# untitled.net
KiCad netlist of a schematic drawn in EAGLE
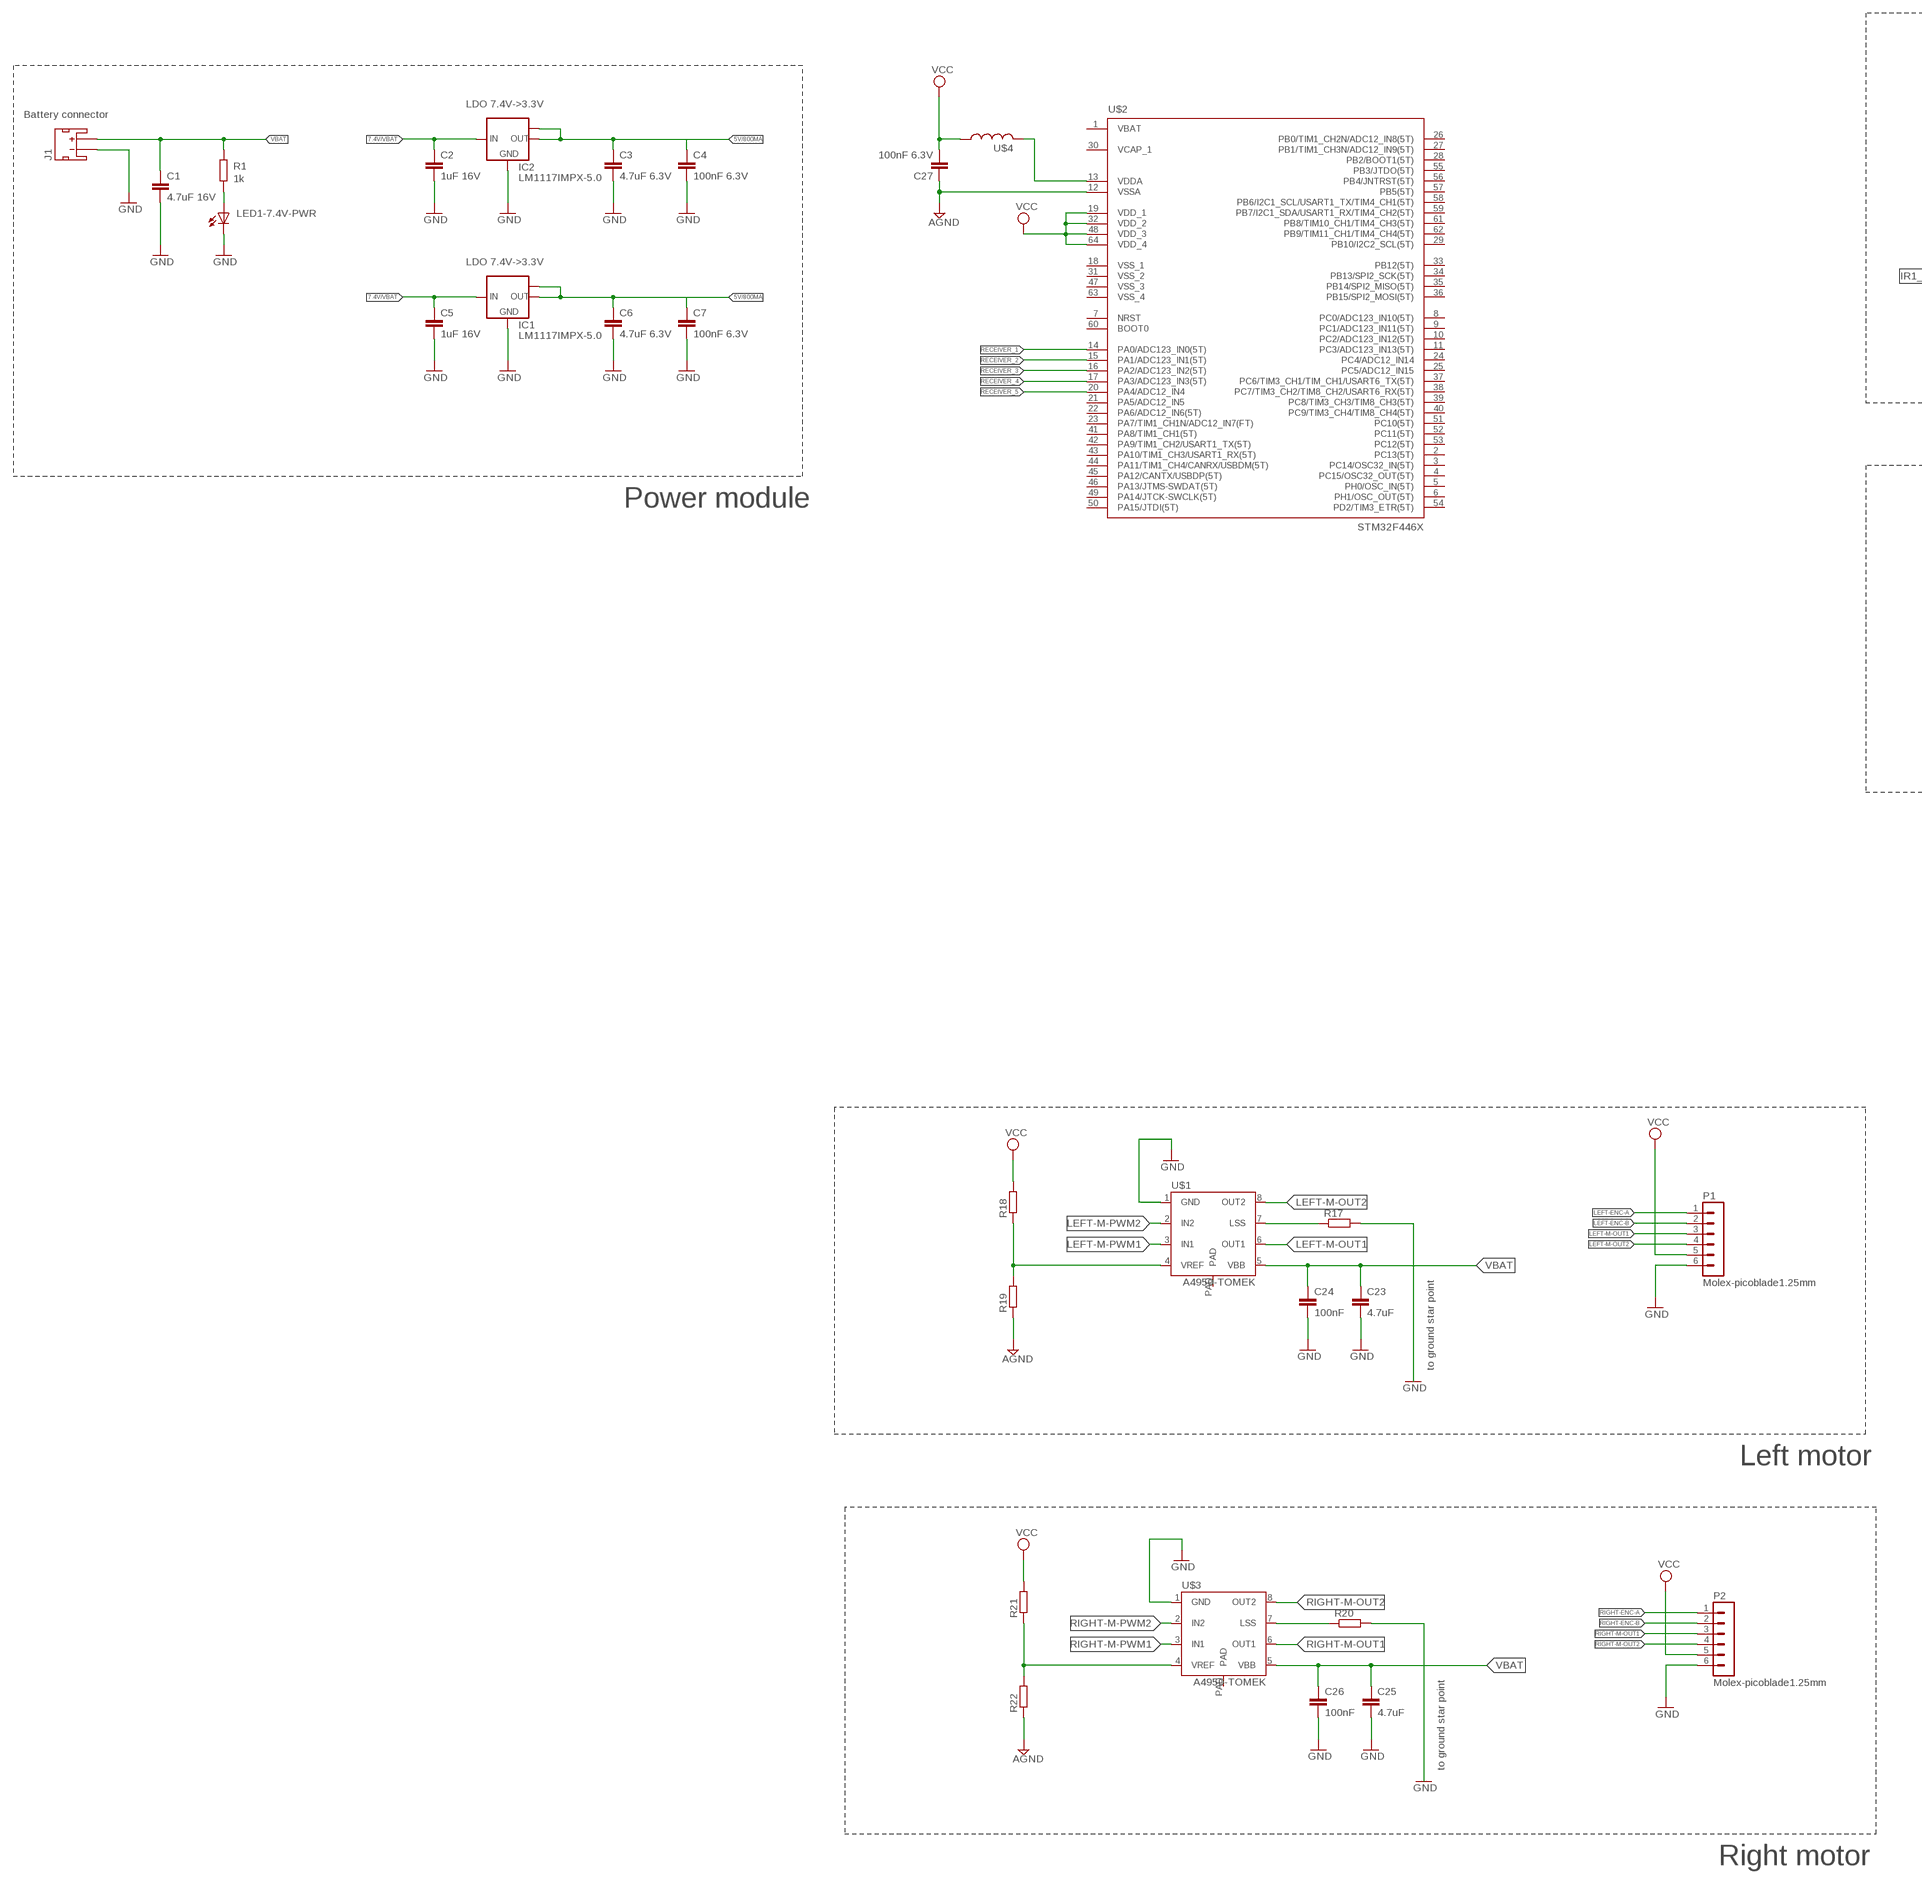
[diagram p0: schematic, sheet 1, part 1 of 2]
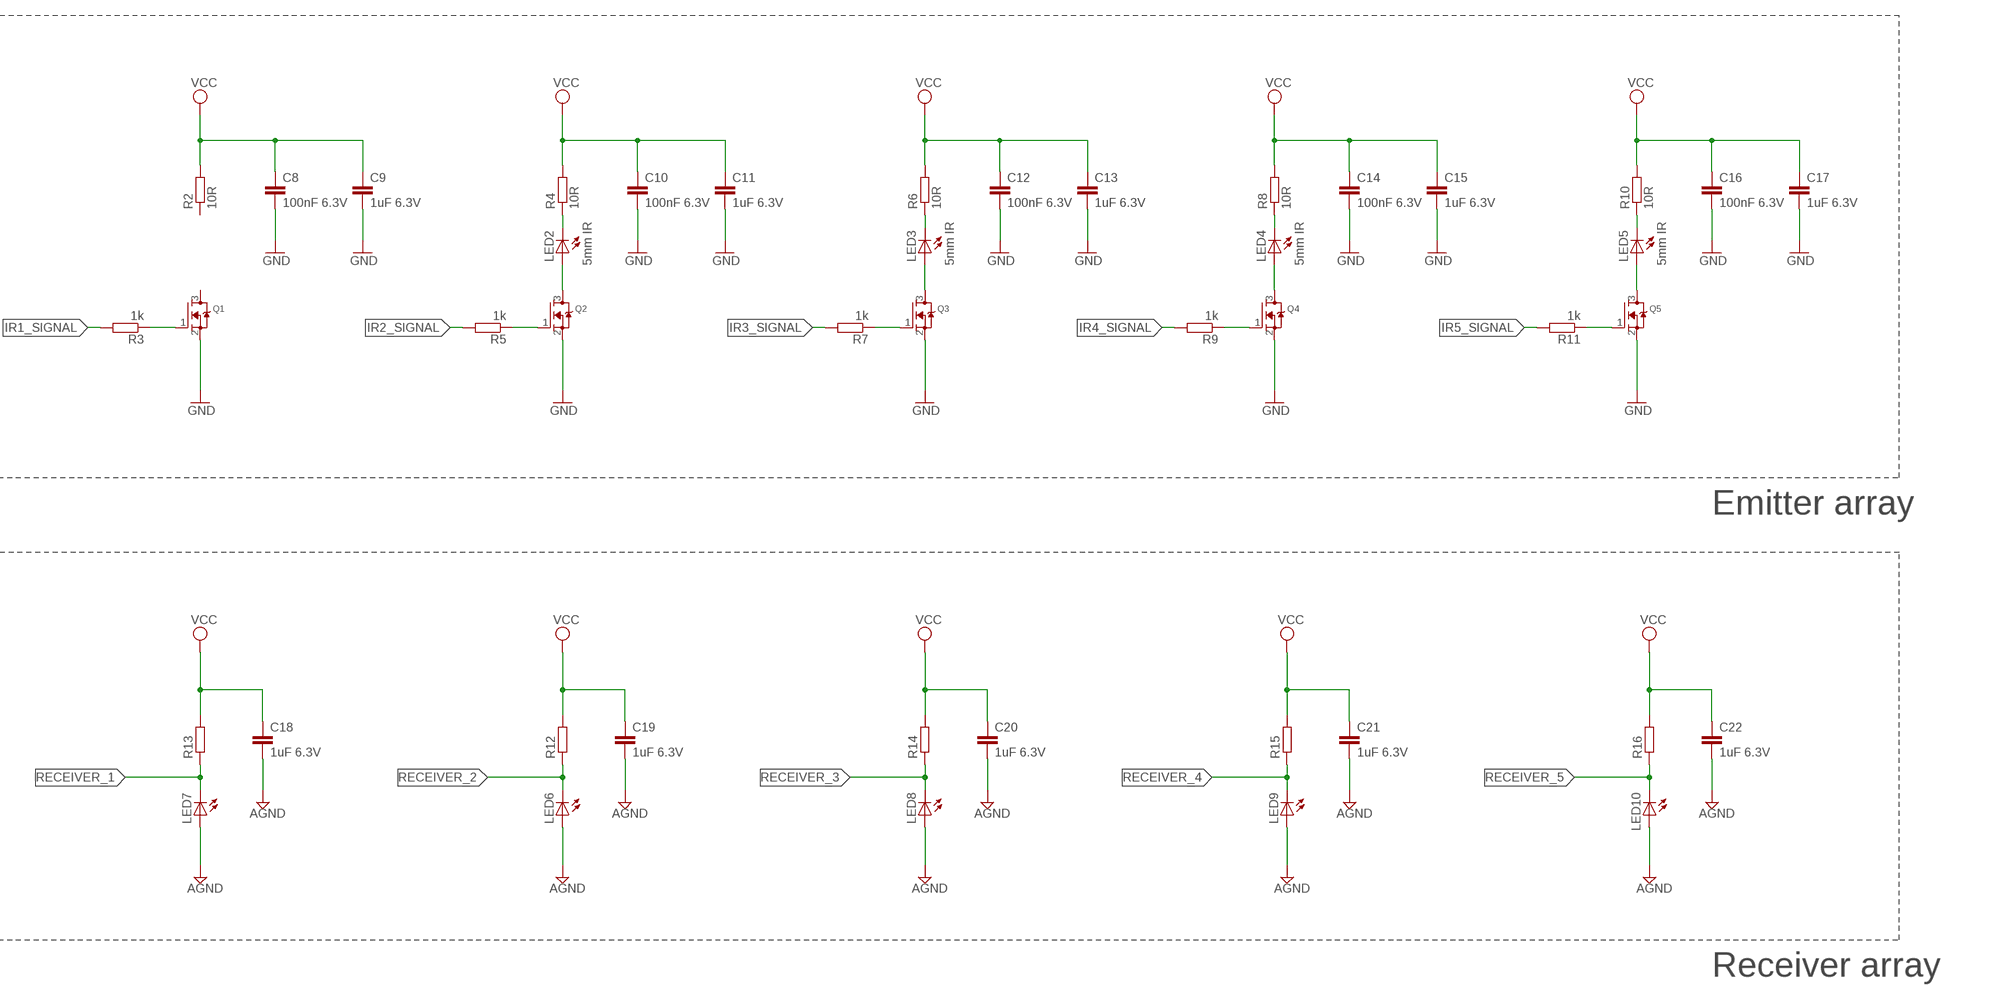
[diagram p1: schematic, sheet 1, part 2 of 2]

(export (version "E")
  (design (tool "Eeschema 10.0.6"))
  (components
    (comp (ref "C1")
      (value "4.7uF 16V")
      (footprint "eagle-import:C0805K")
      (libsource (lib "eagle-import") (part "C-EUC0805K"))
    )
    (comp (ref "C2")
      (value "1uF 16V")
      (footprint "eagle-import:C0805K")
      (libsource (lib "eagle-import") (part "C-EUC0805K"))
    )
    (comp (ref "C3")
      (value "4.7uF 6.3V")
      (footprint "eagle-import:C0805K")
      (libsource (lib "eagle-import") (part "C-EUC0805K"))
    )
    (comp (ref "C4")
      (value "100nF 6.3V")
      (footprint "eagle-import:C0805K")
      (libsource (lib "eagle-import") (part "C-EUC0805K"))
    )
    (comp (ref "C5")
      (value "1uF 16V")
      (footprint "eagle-import:C0805K")
      (libsource (lib "eagle-import") (part "C-EUC0805K"))
    )
    (comp (ref "C6")
      (value "4.7uF 6.3V")
      (footprint "eagle-import:C0805K")
      (libsource (lib "eagle-import") (part "C-EUC0805K"))
    )
    (comp (ref "C7")
      (value "100nF 6.3V")
      (footprint "eagle-import:C0805K")
      (libsource (lib "eagle-import") (part "C-EUC0805K"))
    )
    (comp (ref "C8")
      (value "100nF 6.3V")
      (footprint "eagle-import:C0805K")
      (libsource (lib "eagle-import") (part "C-EUC0805K"))
    )
    (comp (ref "C9")
      (value "1uF 6.3V")
      (footprint "eagle-import:C0805K")
      (libsource (lib "eagle-import") (part "C-EUC0805K"))
    )
    (comp (ref "C10")
      (value "100nF 6.3V")
      (footprint "eagle-import:C0805K")
      (libsource (lib "eagle-import") (part "C-EUC0805K"))
    )
    (comp (ref "C11")
      (value "1uF 6.3V")
      (footprint "eagle-import:C0805K")
      (libsource (lib "eagle-import") (part "C-EUC0805K"))
    )
    (comp (ref "C12")
      (value "100nF 6.3V")
      (footprint "eagle-import:C0805K")
      (libsource (lib "eagle-import") (part "C-EUC0805K"))
    )
    (comp (ref "C13")
      (value "1uF 6.3V")
      (footprint "eagle-import:C0805K")
      (libsource (lib "eagle-import") (part "C-EUC0805K"))
    )
    (comp (ref "C14")
      (value "100nF 6.3V")
      (footprint "eagle-import:C0805K")
      (libsource (lib "eagle-import") (part "C-EUC0805K"))
    )
    (comp (ref "C15")
      (value "1uF 6.3V")
      (footprint "eagle-import:C0805K")
      (libsource (lib "eagle-import") (part "C-EUC0805K"))
    )
    (comp (ref "C16")
      (value "100nF 6.3V")
      (footprint "eagle-import:C0805K")
      (libsource (lib "eagle-import") (part "C-EUC0805K"))
    )
    (comp (ref "C17")
      (value "1uF 6.3V")
      (footprint "eagle-import:C0805K")
      (libsource (lib "eagle-import") (part "C-EUC0805K"))
    )
    (comp (ref "C18")
      (value "1uF 6.3V")
      (footprint "eagle-import:C0805K")
      (libsource (lib "eagle-import") (part "C-EUC0805K"))
    )
    (comp (ref "C19")
      (value "1uF 6.3V")
      (footprint "eagle-import:C0805K")
      (libsource (lib "eagle-import") (part "C-EUC0805K"))
    )
    (comp (ref "C20")
      (value "1uF 6.3V")
      (footprint "eagle-import:C0805K")
      (libsource (lib "eagle-import") (part "C-EUC0805K"))
    )
    (comp (ref "C21")
      (value "1uF 6.3V")
      (footprint "eagle-import:C0805K")
      (libsource (lib "eagle-import") (part "C-EUC0805K"))
    )
    (comp (ref "C22")
      (value "1uF 6.3V")
      (footprint "eagle-import:C0805K")
      (libsource (lib "eagle-import") (part "C-EUC0805K"))
    )
    (comp (ref "C23")
      (value "4.7uF")
      (footprint "eagle-import:C0805K")
      (libsource (lib "eagle-import") (part "C-EUC0805K"))
    )
    (comp (ref "C24")
      (value "100nF")
      (footprint "eagle-import:C0805K")
      (libsource (lib "eagle-import") (part "C-EUC0805K"))
    )
    (comp (ref "C25")
      (value "4.7uF")
      (footprint "eagle-import:C0805K")
      (libsource (lib "eagle-import") (part "C-EUC0805K"))
    )
    (comp (ref "C26")
      (value "100nF")
      (footprint "eagle-import:C0805K")
      (libsource (lib "eagle-import") (part "C-EUC0805K"))
    )
    (comp (ref "C27")
      (value "100nF 6.3V")
      (footprint "eagle-import:C0805K")
      (libsource (lib "eagle-import") (part "C-EUC0805K"))
    )
    (comp (ref "IC1")
      (value "LM1117IMPX-5.0")
      (footprint "eagle-import:SOT223")
      (libsource (lib "eagle-import") (part "LM1117IMPX-5.0"))
    )
    (comp (ref "IC2")
      (value "LM1117IMPX-5.0")
      (footprint "eagle-import:SOT223")
      (libsource (lib "eagle-import") (part "LM1117IMPX-5.0"))
    )
    (comp (ref "J1")
      (value "JST_2MM_MALE")
      (footprint "eagle-import:JST-2-SMD")
      (libsource (lib "eagle-import") (part "JST_2MM_MALE"))
    )
    (comp (ref "LED1-7.4V-PWR")
      (value "LEDCHIP-LED0805")
      (footprint "eagle-import:CHIP-LED0805")
      (libsource (lib "eagle-import") (part "LEDCHIP-LED0805"))
    )
    (comp (ref "LED2")
      (value "5mm IR")
      (footprint "eagle-import:LED5MM")
      (libsource (lib "eagle-import") (part "LED5MM"))
    )
    (comp (ref "LED3")
      (value "5mm IR")
      (footprint "eagle-import:LED5MM")
      (libsource (lib "eagle-import") (part "LED5MM"))
    )
    (comp (ref "LED4")
      (value "5mm IR")
      (footprint "eagle-import:LED5MM")
      (libsource (lib "eagle-import") (part "LED5MM"))
    )
    (comp (ref "LED5")
      (value "5mm IR")
      (footprint "eagle-import:LED5MM")
      (libsource (lib "eagle-import") (part "LED5MM"))
    )
    (comp (ref "LED6")
      (value "LED5MM")
      (footprint "eagle-import:LED5MM")
      (libsource (lib "eagle-import") (part "LED5MM"))
    )
    (comp (ref "LED7")
      (value "LED5MM")
      (footprint "eagle-import:LED5MM")
      (libsource (lib "eagle-import") (part "LED5MM"))
    )
    (comp (ref "LED8")
      (value "LED5MM")
      (footprint "eagle-import:LED5MM")
      (libsource (lib "eagle-import") (part "LED5MM"))
    )
    (comp (ref "LED9")
      (value "LED5MM")
      (footprint "eagle-import:LED5MM")
      (libsource (lib "eagle-import") (part "LED5MM"))
    )
    (comp (ref "LED10")
      (value "LED5MM")
      (footprint "eagle-import:LED5MM")
      (libsource (lib "eagle-import") (part "LED5MM"))
    )
    (comp (ref "P1")
      (value "Molex-picoblade1.25mm")
      (footprint "eagle-import:53398-0610")
      (libsource (lib "eagle-import") (part "53398-0610"))
    )
    (comp (ref "P2")
      (value "Molex-picoblade1.25mm")
      (footprint "eagle-import:53398-0610")
      (libsource (lib "eagle-import") (part "53398-0610"))
    )
    (comp (ref "Q1")
      (value "MOSFET-NREFLOW")
      (footprint "eagle-import:SOT23")
      (libsource (lib "eagle-import") (part "MOSFET-NREFLOW"))
    )
    (comp (ref "Q2")
      (value "MOSFET-NREFLOW")
      (footprint "eagle-import:SOT23")
      (libsource (lib "eagle-import") (part "MOSFET-NREFLOW"))
    )
    (comp (ref "Q3")
      (value "MOSFET-NREFLOW")
      (footprint "eagle-import:SOT23")
      (libsource (lib "eagle-import") (part "MOSFET-NREFLOW"))
    )
    (comp (ref "Q4")
      (value "MOSFET-NREFLOW")
      (footprint "eagle-import:SOT23")
      (libsource (lib "eagle-import") (part "MOSFET-NREFLOW"))
    )
    (comp (ref "Q5")
      (value "MOSFET-NREFLOW")
      (footprint "eagle-import:SOT23")
      (libsource (lib "eagle-import") (part "MOSFET-NREFLOW"))
    )
    (comp (ref "R1")
      (value "1k")
      (footprint "eagle-import:R0805")
      (libsource (lib "eagle-import") (part "resistor_348_R-EU_R0805"))
    )
    (comp (ref "R2")
      (value "10R")
      (footprint "eagle-import:M0805")
      (libsource (lib "eagle-import") (part "R-EU_M0805"))
    )
    (comp (ref "R3")
      (value "1k")
      (footprint "eagle-import:M0805")
      (libsource (lib "eagle-import") (part "R-EU_M0805"))
    )
    (comp (ref "R4")
      (value "10R")
      (footprint "eagle-import:M0805")
      (libsource (lib "eagle-import") (part "R-EU_M0805"))
    )
    (comp (ref "R5")
      (value "1k")
      (footprint "eagle-import:M0805")
      (libsource (lib "eagle-import") (part "R-EU_M0805"))
    )
    (comp (ref "R6")
      (value "10R")
      (footprint "eagle-import:M0805")
      (libsource (lib "eagle-import") (part "R-EU_M0805"))
    )
    (comp (ref "R7")
      (value "1k")
      (footprint "eagle-import:M0805")
      (libsource (lib "eagle-import") (part "R-EU_M0805"))
    )
    (comp (ref "R8")
      (value "10R")
      (footprint "eagle-import:M0805")
      (libsource (lib "eagle-import") (part "R-EU_M0805"))
    )
    (comp (ref "R9")
      (value "1k")
      (footprint "eagle-import:M0805")
      (libsource (lib "eagle-import") (part "R-EU_M0805"))
    )
    (comp (ref "R10")
      (value "10R")
      (footprint "eagle-import:M0805")
      (libsource (lib "eagle-import") (part "R-EU_M0805"))
    )
    (comp (ref "R11")
      (value "1k")
      (footprint "eagle-import:M0805")
      (libsource (lib "eagle-import") (part "R-EU_M0805"))
    )
    (comp (ref "R12")
      (value "R-EU_R0805")
      (footprint "eagle-import:R0805")
      (libsource (lib "eagle-import") (part "R-EU_R0805"))
    )
    (comp (ref "R13")
      (value "R-EU_R0805")
      (footprint "eagle-import:R0805")
      (libsource (lib "eagle-import") (part "R-EU_R0805"))
    )
    (comp (ref "R14")
      (value "R-EU_R0805")
      (footprint "eagle-import:R0805")
      (libsource (lib "eagle-import") (part "R-EU_R0805"))
    )
    (comp (ref "R15")
      (value "R-EU_R0805")
      (footprint "eagle-import:R0805")
      (libsource (lib "eagle-import") (part "R-EU_R0805"))
    )
    (comp (ref "R16")
      (value "R-EU_R0805")
      (footprint "eagle-import:R0805")
      (libsource (lib "eagle-import") (part "R-EU_R0805"))
    )
    (comp (ref "R17")
      (value "R-EU_R2512")
      (footprint "eagle-import:R2512")
      (libsource (lib "eagle-import") (part "R-EU_R2512"))
    )
    (comp (ref "R18")
      (value "R-EU_R0805")
      (footprint "eagle-import:R0805")
      (libsource (lib "eagle-import") (part "R-EU_R0805"))
    )
    (comp (ref "R19")
      (value "R-EU_R0805")
      (footprint "eagle-import:R0805")
      (libsource (lib "eagle-import") (part "R-EU_R0805"))
    )
    (comp (ref "R20")
      (value "R-EU_R2512")
      (footprint "eagle-import:R2512")
      (libsource (lib "eagle-import") (part "R-EU_R2512"))
    )
    (comp (ref "R21")
      (value "R-EU_R0805")
      (footprint "eagle-import:R0805")
      (libsource (lib "eagle-import") (part "R-EU_R0805"))
    )
    (comp (ref "R22")
      (value "R-EU_R0805")
      (footprint "eagle-import:R0805")
      (libsource (lib "eagle-import") (part "R-EU_R0805"))
    )
    (comp (ref "U$1")
      (value "A4950-TOMEK")
      (footprint "eagle-import:SOIC8TP")
      (libsource (lib "eagle-import") (part "A4950-TOMEK"))
    )
    (comp (ref "U$2")
      (value "STM32F446X")
      (footprint "eagle-import:TQFP64")
      (libsource (lib "eagle-import") (part "STM32F446X"))
    )
    (comp (ref "U$3")
      (value "A4950-TOMEK")
      (footprint "eagle-import:SOIC8TP")
      (libsource (lib "eagle-import") (part "A4950-TOMEK"))
    )
    (comp (ref "U$4")
      (value "INDUCTOR_0805_L")
      (footprint "eagle-import:RESC0805_L")
      (libsource (lib "eagle-import") (part "INDUCTOR_0805_L"))
    )
  )
  (nets
    (net (code "1") (name "5V{slash}800MA") (class "Default")
      (node (ref "C3") (pin "1") (pinfunction "1_1") (pintype "passive"))
      (node (ref "C6") (pin "1") (pinfunction "1_1") (pintype "passive"))
      (node (ref "IC1") (pin "2") (pinfunction "OUT_2") (pintype "passive"))
      (node (ref "IC1") (pin "TAB") (pinfunction "OUT1_TAB") (pintype "passive"))
      (node (ref "IC2") (pin "2") (pinfunction "OUT_2") (pintype "passive"))
      (node (ref "IC2") (pin "TAB") (pinfunction "OUT1_TAB") (pintype "passive"))
    )
    (net (code "2") (name "7.4V{slash}VBAT") (class "Default")
      (node (ref "C2") (pin "1") (pinfunction "1_1") (pintype "passive"))
      (node (ref "C5") (pin "1") (pinfunction "1_1") (pintype "passive"))
      (node (ref "IC1") (pin "3") (pinfunction "IN_3") (pintype "input"))
      (node (ref "IC2") (pin "3") (pinfunction "IN_3") (pintype "input"))
    )
    (net (code "3") (name "AGND") (class "Default")
      (node (ref "C18") (pin "2") (pinfunction "2_2") (pintype "passive"))
      (node (ref "C19") (pin "2") (pinfunction "2_2") (pintype "passive"))
      (node (ref "C20") (pin "2") (pinfunction "2_2") (pintype "passive"))
      (node (ref "C21") (pin "2") (pinfunction "2_2") (pintype "passive"))
      (node (ref "C22") (pin "2") (pinfunction "2_2") (pintype "passive"))
      (node (ref "C27") (pin "1") (pinfunction "1_1") (pintype "passive"))
      (node (ref "LED10") (pin "A") (pinfunction "A_A") (pintype "passive"))
      (node (ref "LED6") (pin "A") (pinfunction "A_A") (pintype "passive"))
      (node (ref "LED7") (pin "A") (pinfunction "A_A") (pintype "passive"))
      (node (ref "LED8") (pin "A") (pinfunction "A_A") (pintype "passive"))
      (node (ref "LED9") (pin "A") (pinfunction "A_A") (pintype "passive"))
      (node (ref "R19") (pin "1") (pinfunction "1_1") (pintype "passive"))
      (node (ref "R22") (pin "1") (pinfunction "1_1") (pintype "passive"))
      (node (ref "U$2") (pin "12") (pinfunction "VSSA_12") (pintype "bidirectional"))
    )
    (net (code "4") (name "GND") (class "Default")
      (node (ref "C1") (pin "2") (pinfunction "2_2") (pintype "passive"))
      (node (ref "C10") (pin "2") (pinfunction "2_2") (pintype "passive"))
      (node (ref "C11") (pin "2") (pinfunction "2_2") (pintype "passive"))
      (node (ref "C12") (pin "2") (pinfunction "2_2") (pintype "passive"))
      (node (ref "C13") (pin "2") (pinfunction "2_2") (pintype "passive"))
      (node (ref "C14") (pin "2") (pinfunction "2_2") (pintype "passive"))
      (node (ref "C15") (pin "2") (pinfunction "2_2") (pintype "passive"))
      (node (ref "C16") (pin "2") (pinfunction "2_2") (pintype "passive"))
      (node (ref "C17") (pin "2") (pinfunction "2_2") (pintype "passive"))
      (node (ref "C2") (pin "2") (pinfunction "2_2") (pintype "passive"))
      (node (ref "C23") (pin "2") (pinfunction "2_2") (pintype "passive"))
      (node (ref "C24") (pin "2") (pinfunction "2_2") (pintype "passive"))
      (node (ref "C25") (pin "2") (pinfunction "2_2") (pintype "passive"))
      (node (ref "C26") (pin "2") (pinfunction "2_2") (pintype "passive"))
      (node (ref "C3") (pin "2") (pinfunction "2_2") (pintype "passive"))
      (node (ref "C4") (pin "2") (pinfunction "2_2") (pintype "passive"))
      (node (ref "C5") (pin "2") (pinfunction "2_2") (pintype "passive"))
      (node (ref "C6") (pin "2") (pinfunction "2_2") (pintype "passive"))
      (node (ref "C7") (pin "2") (pinfunction "2_2") (pintype "passive"))
      (node (ref "C8") (pin "2") (pinfunction "2_2") (pintype "passive"))
      (node (ref "C9") (pin "2") (pinfunction "2_2") (pintype "passive"))
      (node (ref "IC1") (pin "1") (pinfunction "GND_1") (pintype "input"))
      (node (ref "IC2") (pin "1") (pinfunction "GND_1") (pintype "input"))
      (node (ref "J1") (pin "1") (pinfunction "-_1") (pintype "bidirectional"))
      (node (ref "LED1-7.4V-PWR") (pin "C") (pinfunction "C_C") (pintype "passive"))
      (node (ref "P1") (pin "6") (pinfunction "6_6") (pintype "passive"))
      (node (ref "P2") (pin "6") (pinfunction "6_6") (pintype "passive"))
      (node (ref "Q1") (pin "2") (pinfunction "S_2") (pintype "bidirectional"))
      (node (ref "Q2") (pin "2") (pinfunction "S_2") (pintype "bidirectional"))
      (node (ref "Q3") (pin "2") (pinfunction "S_2") (pintype "bidirectional"))
      (node (ref "Q4") (pin "2") (pinfunction "S_2") (pintype "bidirectional"))
      (node (ref "Q5") (pin "2") (pinfunction "S_2") (pintype "bidirectional"))
      (node (ref "R17") (pin "2") (pinfunction "2_2") (pintype "passive"))
      (node (ref "R20") (pin "2") (pinfunction "2_2") (pintype "passive"))
      (node (ref "U$1") (pin "1") (pinfunction "GND_1") (pintype "bidirectional"))
      (node (ref "U$3") (pin "1") (pinfunction "GND_1") (pintype "bidirectional"))
    )
    (net (code "5") (name "IR1_SIGNAL") (class "Default")
      (node (ref "R3") (pin "2") (pinfunction "2_2") (pintype "passive"))
    )
    (net (code "6") (name "IR2_SIGNAL") (class "Default")
      (node (ref "R5") (pin "2") (pinfunction "2_2") (pintype "passive"))
    )
    (net (code "7") (name "IR3_SIGNAL") (class "Default")
      (node (ref "R7") (pin "2") (pinfunction "2_2") (pintype "passive"))
    )
    (net (code "8") (name "IR4_SIGNAL") (class "Default")
      (node (ref "R9") (pin "2") (pinfunction "2_2") (pintype "passive"))
    )
    (net (code "9") (name "IR5_SIGNAL") (class "Default")
      (node (ref "R11") (pin "2") (pinfunction "2_2") (pintype "passive"))
    )
    (net (code "10") (name "LEFT-ENC-A") (class "Default")
      (node (ref "P1") (pin "1") (pinfunction "1_1") (pintype "passive"))
    )
    (net (code "11") (name "LEFT-ENC-B") (class "Default")
      (node (ref "P1") (pin "2") (pinfunction "2_2") (pintype "passive"))
    )
    (net (code "12") (name "LEFT-M-OUT1") (class "Default")
      (node (ref "P1") (pin "3") (pinfunction "3_3") (pintype "passive"))
      (node (ref "U$1") (pin "6") (pinfunction "OUT1_6") (pintype "bidirectional"))
    )
    (net (code "13") (name "LEFT-M-OUT2") (class "Default")
      (node (ref "P1") (pin "4") (pinfunction "4_4") (pintype "passive"))
      (node (ref "U$1") (pin "8") (pinfunction "OUT2_8") (pintype "bidirectional"))
    )
    (net (code "14") (name "LEFT-M-PWM1") (class "Default")
      (node (ref "U$1") (pin "3") (pinfunction "IN1_3") (pintype "bidirectional"))
    )
    (net (code "15") (name "LEFT-M-PWM2") (class "Default")
      (node (ref "U$1") (pin "2") (pinfunction "IN2_2") (pintype "bidirectional"))
    )
    (net (code "16") (name "Net-(LED1-7.4V-PWR-PadA)") (class "Default")
      (node (ref "LED1-7.4V-PWR") (pin "A") (pinfunction "A_A") (pintype "passive"))
      (node (ref "R1") (pin "1") (pinfunction "1_1") (pintype "passive"))
    )
    (net (code "17") (name "Net-(LED2-C)") (class "Default")
      (node (ref "LED2") (pin "K") (pinfunction "C_K") (pintype "passive"))
      (node (ref "R4") (pin "1") (pinfunction "1_1") (pintype "passive"))
    )
    (net (code "18") (name "Net-(LED3-C)") (class "Default")
      (node (ref "LED3") (pin "K") (pinfunction "C_K") (pintype "passive"))
      (node (ref "R6") (pin "1") (pinfunction "1_1") (pintype "passive"))
    )
    (net (code "19") (name "Net-(LED4-C)") (class "Default")
      (node (ref "LED4") (pin "K") (pinfunction "C_K") (pintype "passive"))
      (node (ref "R8") (pin "1") (pinfunction "1_1") (pintype "passive"))
    )
    (net (code "20") (name "Net-(LED5-C)") (class "Default")
      (node (ref "LED5") (pin "K") (pinfunction "C_K") (pintype "passive"))
      (node (ref "R10") (pin "1") (pinfunction "1_1") (pintype "passive"))
    )
    (net (code "21") (name "Net-(Q1-G)") (class "Default")
      (node (ref "Q1") (pin "1") (pinfunction "G_1") (pintype "bidirectional"))
      (node (ref "R3") (pin "1") (pinfunction "1_1") (pintype "passive"))
    )
    (net (code "22") (name "Net-(Q2-D)") (class "Default")
      (node (ref "LED2") (pin "A") (pinfunction "A_A") (pintype "passive"))
      (node (ref "Q2") (pin "3") (pinfunction "D_3") (pintype "bidirectional"))
    )
    (net (code "23") (name "Net-(Q2-G)") (class "Default")
      (node (ref "Q2") (pin "1") (pinfunction "G_1") (pintype "bidirectional"))
      (node (ref "R5") (pin "1") (pinfunction "1_1") (pintype "passive"))
    )
    (net (code "24") (name "Net-(Q3-D)") (class "Default")
      (node (ref "LED3") (pin "A") (pinfunction "A_A") (pintype "passive"))
      (node (ref "Q3") (pin "3") (pinfunction "D_3") (pintype "bidirectional"))
    )
    (net (code "25") (name "Net-(Q3-G)") (class "Default")
      (node (ref "Q3") (pin "1") (pinfunction "G_1") (pintype "bidirectional"))
      (node (ref "R7") (pin "1") (pinfunction "1_1") (pintype "passive"))
    )
    (net (code "26") (name "Net-(Q4-D)") (class "Default")
      (node (ref "LED4") (pin "A") (pinfunction "A_A") (pintype "passive"))
      (node (ref "Q4") (pin "3") (pinfunction "D_3") (pintype "bidirectional"))
    )
    (net (code "27") (name "Net-(Q4-G)") (class "Default")
      (node (ref "Q4") (pin "1") (pinfunction "G_1") (pintype "bidirectional"))
      (node (ref "R9") (pin "1") (pinfunction "1_1") (pintype "passive"))
    )
    (net (code "28") (name "Net-(Q5-D)") (class "Default")
      (node (ref "LED5") (pin "A") (pinfunction "A_A") (pintype "passive"))
      (node (ref "Q5") (pin "3") (pinfunction "D_3") (pintype "bidirectional"))
    )
    (net (code "29") (name "Net-(Q5-G)") (class "Default")
      (node (ref "Q5") (pin "1") (pinfunction "G_1") (pintype "bidirectional"))
      (node (ref "R11") (pin "1") (pinfunction "1_1") (pintype "passive"))
    )
    (net (code "30") (name "Net-(U$1-LSS)") (class "Default")
      (node (ref "R17") (pin "1") (pinfunction "1_1") (pintype "passive"))
      (node (ref "U$1") (pin "7") (pinfunction "LSS_7") (pintype "bidirectional"))
    )
    (net (code "31") (name "Net-(U$1-VREF)") (class "Default")
      (node (ref "R18") (pin "1") (pinfunction "1_1") (pintype "passive"))
      (node (ref "R19") (pin "2") (pinfunction "2_2") (pintype "passive"))
      (node (ref "U$1") (pin "4") (pinfunction "VREF_4") (pintype "bidirectional"))
    )
    (net (code "32") (name "Net-(U$2-VDDA)") (class "Default")
      (node (ref "U$2") (pin "13") (pinfunction "VDDA_13") (pintype "bidirectional"))
      (node (ref "U$4") (pin "2") (pinfunction "2_2") (pintype "passive"))
    )
    (net (code "33") (name "Net-(U$3-LSS)") (class "Default")
      (node (ref "R20") (pin "1") (pinfunction "1_1") (pintype "passive"))
      (node (ref "U$3") (pin "7") (pinfunction "LSS_7") (pintype "bidirectional"))
    )
    (net (code "34") (name "Net-(U$3-VREF)") (class "Default")
      (node (ref "R21") (pin "1") (pinfunction "1_1") (pintype "passive"))
      (node (ref "R22") (pin "2") (pinfunction "2_2") (pintype "passive"))
      (node (ref "U$3") (pin "4") (pinfunction "VREF_4") (pintype "bidirectional"))
    )
    (net (code "35") (name "RECEIVER_1") (class "Default")
      (node (ref "LED7") (pin "K") (pinfunction "C_K") (pintype "passive"))
      (node (ref "R13") (pin "1") (pinfunction "1_1") (pintype "passive"))
      (node (ref "U$2") (pin "14") (pinfunction "PA0/ADC123_IN0(5T)_14") (pintype "bidirectional"))
    )
    (net (code "36") (name "RECEIVER_2") (class "Default")
      (node (ref "LED6") (pin "K") (pinfunction "C_K") (pintype "passive"))
      (node (ref "R12") (pin "1") (pinfunction "1_1") (pintype "passive"))
      (node (ref "U$2") (pin "15") (pinfunction "PA1/ADC123_IN1(5T)_15") (pintype "bidirectional"))
    )
    (net (code "37") (name "RECEIVER_3") (class "Default")
      (node (ref "LED8") (pin "K") (pinfunction "C_K") (pintype "passive"))
      (node (ref "R14") (pin "1") (pinfunction "1_1") (pintype "passive"))
      (node (ref "U$2") (pin "16") (pinfunction "PA2/ADC123_IN2(5T)_16") (pintype "bidirectional"))
    )
    (net (code "38") (name "RECEIVER_4") (class "Default")
      (node (ref "LED9") (pin "K") (pinfunction "C_K") (pintype "passive"))
      (node (ref "R15") (pin "1") (pinfunction "1_1") (pintype "passive"))
      (node (ref "U$2") (pin "17") (pinfunction "PA3/ADC123_IN3(5T)_17") (pintype "bidirectional"))
    )
    (net (code "39") (name "RECEIVER_5") (class "Default")
      (node (ref "LED10") (pin "K") (pinfunction "C_K") (pintype "passive"))
      (node (ref "R16") (pin "1") (pinfunction "1_1") (pintype "passive"))
      (node (ref "U$2") (pin "20") (pinfunction "PA4/ADC12_IN4_20") (pintype "bidirectional"))
    )
    (net (code "40") (name "RIGHT-ENC-A") (class "Default")
      (node (ref "P2") (pin "1") (pinfunction "1_1") (pintype "passive"))
    )
    (net (code "41") (name "RIGHT-ENC-B") (class "Default")
      (node (ref "P2") (pin "2") (pinfunction "2_2") (pintype "passive"))
    )
    (net (code "42") (name "RIGHT-M-OUT1") (class "Default")
      (node (ref "P2") (pin "3") (pinfunction "3_3") (pintype "passive"))
      (node (ref "U$3") (pin "6") (pinfunction "OUT1_6") (pintype "bidirectional"))
    )
    (net (code "43") (name "RIGHT-M-OUT2") (class "Default")
      (node (ref "P2") (pin "4") (pinfunction "4_4") (pintype "passive"))
      (node (ref "U$3") (pin "8") (pinfunction "OUT2_8") (pintype "bidirectional"))
    )
    (net (code "44") (name "RIGHT-M-PWM1") (class "Default")
      (node (ref "U$3") (pin "3") (pinfunction "IN1_3") (pintype "bidirectional"))
    )
    (net (code "45") (name "RIGHT-M-PWM2") (class "Default")
      (node (ref "U$3") (pin "2") (pinfunction "IN2_2") (pintype "bidirectional"))
    )
    (net (code "46") (name "VBAT") (class "Default")
      (node (ref "C1") (pin "1") (pinfunction "1_1") (pintype "passive"))
      (node (ref "C23") (pin "1") (pinfunction "1_1") (pintype "passive"))
      (node (ref "C24") (pin "1") (pinfunction "1_1") (pintype "passive"))
      (node (ref "C25") (pin "1") (pinfunction "1_1") (pintype "passive"))
      (node (ref "C26") (pin "1") (pinfunction "1_1") (pintype "passive"))
      (node (ref "J1") (pin "2") (pinfunction "+_2") (pintype "bidirectional"))
      (node (ref "R1") (pin "2") (pinfunction "2_2") (pintype "passive"))
      (node (ref "U$1") (pin "5") (pinfunction "VBB_5") (pintype "bidirectional"))
      (node (ref "U$3") (pin "5") (pinfunction "VBB_5") (pintype "bidirectional"))
    )
    (net (code "47") (name "VCC") (class "Default")
      (node (ref "C10") (pin "1") (pinfunction "1_1") (pintype "passive"))
      (node (ref "C11") (pin "1") (pinfunction "1_1") (pintype "passive"))
      (node (ref "C12") (pin "1") (pinfunction "1_1") (pintype "passive"))
      (node (ref "C13") (pin "1") (pinfunction "1_1") (pintype "passive"))
      (node (ref "C14") (pin "1") (pinfunction "1_1") (pintype "passive"))
      (node (ref "C15") (pin "1") (pinfunction "1_1") (pintype "passive"))
      (node (ref "C16") (pin "1") (pinfunction "1_1") (pintype "passive"))
      (node (ref "C17") (pin "1") (pinfunction "1_1") (pintype "passive"))
      (node (ref "C18") (pin "1") (pinfunction "1_1") (pintype "passive"))
      (node (ref "C19") (pin "1") (pinfunction "1_1") (pintype "passive"))
      (node (ref "C20") (pin "1") (pinfunction "1_1") (pintype "passive"))
      (node (ref "C21") (pin "1") (pinfunction "1_1") (pintype "passive"))
      (node (ref "C22") (pin "1") (pinfunction "1_1") (pintype "passive"))
      (node (ref "C27") (pin "2") (pinfunction "2_2") (pintype "passive"))
      (node (ref "C8") (pin "1") (pinfunction "1_1") (pintype "passive"))
      (node (ref "C9") (pin "1") (pinfunction "1_1") (pintype "passive"))
      (node (ref "P1") (pin "5") (pinfunction "5_5") (pintype "passive"))
      (node (ref "P2") (pin "5") (pinfunction "5_5") (pintype "passive"))
      (node (ref "R10") (pin "2") (pinfunction "2_2") (pintype "passive"))
      (node (ref "R12") (pin "2") (pinfunction "2_2") (pintype "passive"))
      (node (ref "R13") (pin "2") (pinfunction "2_2") (pintype "passive"))
      (node (ref "R14") (pin "2") (pinfunction "2_2") (pintype "passive"))
      (node (ref "R15") (pin "2") (pinfunction "2_2") (pintype "passive"))
      (node (ref "R16") (pin "2") (pinfunction "2_2") (pintype "passive"))
      (node (ref "R18") (pin "2") (pinfunction "2_2") (pintype "passive"))
      (node (ref "R2") (pin "2") (pinfunction "2_2") (pintype "passive"))
      (node (ref "R21") (pin "2") (pinfunction "2_2") (pintype "passive"))
      (node (ref "R4") (pin "2") (pinfunction "2_2") (pintype "passive"))
      (node (ref "R6") (pin "2") (pinfunction "2_2") (pintype "passive"))
      (node (ref "R8") (pin "2") (pinfunction "2_2") (pintype "passive"))
      (node (ref "U$2") (pin "19") (pinfunction "VDD_1_19") (pintype "bidirectional"))
      (node (ref "U$2") (pin "32") (pinfunction "VDD_2_32") (pintype "bidirectional"))
      (node (ref "U$2") (pin "48") (pinfunction "VDD_3_48") (pintype "bidirectional"))
      (node (ref "U$2") (pin "64") (pinfunction "VDD_4_64") (pintype "bidirectional"))
      (node (ref "U$4") (pin "1") (pinfunction "1_1") (pintype "passive"))
    )
    (net (code "48") (name "unconnected-(C4-Pad1)") (class "Default")
      (node (ref "C4") (pin "1") (pinfunction "1_1") (pintype "passive"))
    )
    (net (code "49") (name "unconnected-(C7-Pad1)") (class "Default")
      (node (ref "C7") (pin "1") (pinfunction "1_1") (pintype "passive"))
    )
    (net (code "50") (name "unconnected-(J1-PAD1-PadNC1)") (class "Default")
      (node (ref "J1") (pin "NC1") (pinfunction "PAD1_NC1") (pintype "bidirectional"))
    )
    (net (code "51") (name "unconnected-(J1-PAD2-PadNC2)") (class "Default")
      (node (ref "J1") (pin "NC2") (pinfunction "PAD2_NC2") (pintype "bidirectional"))
    )
    (net (code "52") (name "unconnected-(Q1-D-Pad3)") (class "Default")
      (node (ref "Q1") (pin "3") (pinfunction "D_3") (pintype "bidirectional"))
    )
    (net (code "53") (name "unconnected-(R2-Pad1)") (class "Default")
      (node (ref "R2") (pin "1") (pinfunction "1_1") (pintype "passive"))
    )
    (net (code "54") (name "unconnected-(U$1-PadPAD)") (class "Default")
      (node (ref "U$1") (pin "PAD") (pinfunction "PAD_PAD") (pintype "bidirectional"))
    )
    (net (code "55") (name "unconnected-(U$2-BOOT0-Pad60)") (class "Default")
      (node (ref "U$2") (pin "60") (pinfunction "BOOT0_60") (pintype "bidirectional"))
    )
    (net (code "56") (name "unconnected-(U$2-NRST-Pad7)") (class "Default")
      (node (ref "U$2") (pin "7") (pinfunction "NRST_7") (pintype "bidirectional"))
    )
    (net (code "57") (name "unconnected-(U$2-PA5{slash}ADC12_IN5-Pad21)") (class "Default")
      (node (ref "U$2") (pin "21") (pinfunction "PA5/ADC12_IN5_21") (pintype "bidirectional"))
    )
    (net (code "58") (name "unconnected-(U$2-PA6{slash}ADC12_IN6(5T)-Pad22)") (class "Default")
      (node (ref "U$2") (pin "22") (pinfunction "PA6/ADC12_IN6(5T)_22") (pintype "bidirectional"))
    )
    (net (code "59") (name "unconnected-(U$2-PA7{slash}TIM1_CH1N{slash}ADC12_IN7(FT)-Pad23)") (class "Default")
      (node (ref "U$2") (pin "23") (pinfunction "PA7/TIM1_CH1N/ADC12_IN7(FT)_23") (pintype "bidirectional"))
    )
    (net (code "60") (name "unconnected-(U$2-PA8{slash}TIM1_CH1(5T)-Pad41)") (class "Default")
      (node (ref "U$2") (pin "41") (pinfunction "PA8/TIM1_CH1(5T)_41") (pintype "bidirectional"))
    )
    (net (code "61") (name "unconnected-(U$2-PA9{slash}TIM1_CH2{slash}USART1_TX(5T)-Pad42)") (class "Default")
      (node (ref "U$2") (pin "42") (pinfunction "PA9/TIM1_CH2/USART1_TX(5T)_42") (pintype "bidirectional"))
    )
    (net (code "62") (name "unconnected-(U$2-PA10{slash}TIM1_CH3{slash}USART1_RX(5T)-Pad43)") (class "Default")
      (node (ref "U$2") (pin "43") (pinfunction "PA10/TIM1_CH3/USART1_RX(5T)_43") (pintype "bidirectional"))
    )
    (net (code "63") (name "unconnected-(U$2-PA11{slash}TIM1_CH4{slash}CANRX{slash}USBDM(5T)-Pad44)") (class "Default")
      (node (ref "U$2") (pin "44") (pinfunction "PA11/TIM1_CH4/CANRX/USBDM(5T)_44") (pintype "bidirectional"))
    )
    (net (code "64") (name "unconnected-(U$2-PA12{slash}CANTX{slash}USBDP(5T)-Pad45)") (class "Default")
      (node (ref "U$2") (pin "45") (pinfunction "PA12/CANTX/USBDP(5T)_45") (pintype "bidirectional"))
    )
    (net (code "65") (name "unconnected-(U$2-PA13{slash}JTMS-SWDAT(5T)-Pad46)") (class "Default")
      (node (ref "U$2") (pin "46") (pinfunction "PA13/JTMS-SWDAT(5T)_46") (pintype "bidirectional"))
    )
    (net (code "66") (name "unconnected-(U$2-PA14{slash}JTCK-SWCLK(5T)-Pad49)") (class "Default")
      (node (ref "U$2") (pin "49") (pinfunction "PA14/JTCK-SWCLK(5T)_49") (pintype "bidirectional"))
    )
    (net (code "67") (name "unconnected-(U$2-PA15{slash}JTDI(5T)-Pad50)") (class "Default")
      (node (ref "U$2") (pin "50") (pinfunction "PA15/JTDI(5T)_50") (pintype "bidirectional"))
    )
    (net (code "68") (name "unconnected-(U$2-PB0{slash}TIM1_CH2N{slash}ADC12_IN8(5T)-Pad26)") (class "Default")
      (node (ref "U$2") (pin "26") (pinfunction "PB0/TIM1_CH2N/ADC12_IN8(5T)_26") (pintype "bidirectional"))
    )
    (net (code "69") (name "unconnected-(U$2-PB1{slash}TIM1_CH3N{slash}ADC12_IN9(5T)-Pad27)") (class "Default")
      (node (ref "U$2") (pin "27") (pinfunction "PB1/TIM1_CH3N/ADC12_IN9(5T)_27") (pintype "bidirectional"))
    )
    (net (code "70") (name "unconnected-(U$2-PB2{slash}BOOT1(5T)-Pad28)") (class "Default")
      (node (ref "U$2") (pin "28") (pinfunction "PB2/BOOT1(5T)_28") (pintype "bidirectional"))
    )
    (net (code "71") (name "unconnected-(U$2-PB3{slash}JTDO(5T)-Pad55)") (class "Default")
      (node (ref "U$2") (pin "55") (pinfunction "PB3/JTDO(5T)_55") (pintype "bidirectional"))
    )
    (net (code "72") (name "unconnected-(U$2-PB4{slash}JNTRST(5T)-Pad56)") (class "Default")
      (node (ref "U$2") (pin "56") (pinfunction "PB4/JNTRST(5T)_56") (pintype "bidirectional"))
    )
    (net (code "73") (name "unconnected-(U$2-PB5(5T)-Pad57)") (class "Default")
      (node (ref "U$2") (pin "57") (pinfunction "PB5(5T)_57") (pintype "bidirectional"))
    )
    (net (code "74") (name "unconnected-(U$2-PB6{slash}I2C1_SCL{slash}USART1_TX{slash}TIM4_CH1(5T)-Pad58)") (class "Default")
      (node (ref "U$2") (pin "58") (pinfunction "PB6/I2C1_SCL/USART1_TX/TIM4_CH1(5T)_58") (pintype "bidirectional"))
    )
    (net (code "75") (name "unconnected-(U$2-PB7{slash}I2C1_SDA{slash}USART1_RX{slash}TIM4_CH2(5T)-Pad59)") (class "Default")
      (node (ref "U$2") (pin "59") (pinfunction "PB7/I2C1_SDA/USART1_RX/TIM4_CH2(5T)_59") (pintype "bidirectional"))
    )
    (net (code "76") (name "unconnected-(U$2-PB8{slash}TIM10_CH1{slash}TIM4_CH3(5T)-Pad61)") (class "Default")
      (node (ref "U$2") (pin "61") (pinfunction "PB8/TIM10_CH1/TIM4_CH3(5T)_61") (pintype "bidirectional"))
    )
    (net (code "77") (name "unconnected-(U$2-PB9{slash}TIM11_CH1{slash}TIM4_CH4(5T)-Pad62)") (class "Default")
      (node (ref "U$2") (pin "62") (pinfunction "PB9/TIM11_CH1/TIM4_CH4(5T)_62") (pintype "bidirectional"))
    )
    (net (code "78") (name "unconnected-(U$2-PB10{slash}I2C2_SCL(5T)-Pad29)") (class "Default")
      (node (ref "U$2") (pin "29") (pinfunction "PB10/I2C2_SCL(5T)_29") (pintype "bidirectional"))
    )
    (net (code "79") (name "unconnected-(U$2-PB12(5T)-Pad33)") (class "Default")
      (node (ref "U$2") (pin "33") (pinfunction "PB12(5T)_33") (pintype "bidirectional"))
    )
    (net (code "80") (name "unconnected-(U$2-PB13{slash}SPI2_SCK(5T)-Pad34)") (class "Default")
      (node (ref "U$2") (pin "34") (pinfunction "PB13/SPI2_SCK(5T)_34") (pintype "bidirectional"))
    )
    (net (code "81") (name "unconnected-(U$2-PB14{slash}SPI2_MISO(5T)-Pad35)") (class "Default")
      (node (ref "U$2") (pin "35") (pinfunction "PB14/SPI2_MISO(5T)_35") (pintype "bidirectional"))
    )
    (net (code "82") (name "unconnected-(U$2-PB15{slash}SPI2_MOSI(5T)-Pad36)") (class "Default")
      (node (ref "U$2") (pin "36") (pinfunction "PB15/SPI2_MOSI(5T)_36") (pintype "bidirectional"))
    )
    (net (code "83") (name "unconnected-(U$2-PC0{slash}ADC123_IN10(5T)-Pad8)") (class "Default")
      (node (ref "U$2") (pin "8") (pinfunction "PC0/ADC123_IN10(5T)_8") (pintype "bidirectional"))
    )
    (net (code "84") (name "unconnected-(U$2-PC1{slash}ADC123_IN11(5T)-Pad9)") (class "Default")
      (node (ref "U$2") (pin "9") (pinfunction "PC1/ADC123_IN11(5T)_9") (pintype "bidirectional"))
    )
    (net (code "85") (name "unconnected-(U$2-PC2{slash}ADC123_IN12(5T)-Pad10)") (class "Default")
      (node (ref "U$2") (pin "10") (pinfunction "PC2/ADC123_IN12(5T)_10") (pintype "bidirectional"))
    )
    (net (code "86") (name "unconnected-(U$2-PC3{slash}ADC123_IN13(5T)-Pad11)") (class "Default")
      (node (ref "U$2") (pin "11") (pinfunction "PC3/ADC123_IN13(5T)_11") (pintype "bidirectional"))
    )
    (net (code "87") (name "unconnected-(U$2-PC4{slash}ADC12_IN14-Pad24)") (class "Default")
      (node (ref "U$2") (pin "24") (pinfunction "PC4/ADC12_IN14_24") (pintype "bidirectional"))
    )
    (net (code "88") (name "unconnected-(U$2-PC5{slash}ADC12_IN15-Pad25)") (class "Default")
      (node (ref "U$2") (pin "25") (pinfunction "PC5/ADC12_IN15_25") (pintype "bidirectional"))
    )
    (net (code "89") (name "unconnected-(U$2-PC6{slash}TIM3_CH1{slash}TIM_CH1{slash}USART6_TX(5T)-Pad37)") (class "Default")
      (node (ref "U$2") (pin "37") (pinfunction "PC6/TIM3_CH1/TIM_CH1/USART6_TX(5T)_37") (pintype "bidirectional"))
    )
    (net (code "90") (name "unconnected-(U$2-PC7{slash}TIM3_CH2{slash}TIM8_CH2{slash}USART6_RX(5T)-Pad38)") (class "Default")
      (node (ref "U$2") (pin "38") (pinfunction "PC7/TIM3_CH2/TIM8_CH2/USART6_RX(5T)_38") (pintype "bidirectional"))
    )
    (net (code "91") (name "unconnected-(U$2-PC8{slash}TIM3_CH3{slash}TIM8_CH3(5T)-Pad39)") (class "Default")
      (node (ref "U$2") (pin "39") (pinfunction "PC8/TIM3_CH3/TIM8_CH3(5T)_39") (pintype "bidirectional"))
    )
    (net (code "92") (name "unconnected-(U$2-PC9{slash}TIM3_CH4{slash}TIM8_CH4(5T)-Pad40)") (class "Default")
      (node (ref "U$2") (pin "40") (pinfunction "PC9/TIM3_CH4/TIM8_CH4(5T)_40") (pintype "bidirectional"))
    )
    (net (code "93") (name "unconnected-(U$2-PC10(5T)-Pad51)") (class "Default")
      (node (ref "U$2") (pin "51") (pinfunction "PC10(5T)_51") (pintype "bidirectional"))
    )
    (net (code "94") (name "unconnected-(U$2-PC11(5T)-Pad52)") (class "Default")
      (node (ref "U$2") (pin "52") (pinfunction "PC11(5T)_52") (pintype "bidirectional"))
    )
    (net (code "95") (name "unconnected-(U$2-PC12(5T)-Pad53)") (class "Default")
      (node (ref "U$2") (pin "53") (pinfunction "PC12(5T)_53") (pintype "bidirectional"))
    )
    (net (code "96") (name "unconnected-(U$2-PC13(5T)-Pad2)") (class "Default")
      (node (ref "U$2") (pin "2") (pinfunction "PC13(5T)_2") (pintype "bidirectional"))
    )
    (net (code "97") (name "unconnected-(U$2-PC14{slash}OSC32_IN(5T)-Pad3)") (class "Default")
      (node (ref "U$2") (pin "3") (pinfunction "PC14/OSC32_IN(5T)_3") (pintype "bidirectional"))
    )
    (net (code "98") (name "unconnected-(U$2-PC15{slash}OSC32_OUT(5T)-Pad4)") (class "Default")
      (node (ref "U$2") (pin "4") (pinfunction "PC15/OSC32_OUT(5T)_4") (pintype "bidirectional"))
    )
    (net (code "99") (name "unconnected-(U$2-PD2{slash}TIM3_ETR(5T)-Pad54)") (class "Default")
      (node (ref "U$2") (pin "54") (pinfunction "PD2/TIM3_ETR(5T)_54") (pintype "bidirectional"))
    )
    (net (code "100") (name "unconnected-(U$2-PH0{slash}OSC_IN(5T)-Pad5)") (class "Default")
      (node (ref "U$2") (pin "5") (pinfunction "PH0/OSC_IN(5T)_5") (pintype "bidirectional"))
    )
    (net (code "101") (name "unconnected-(U$2-PH1{slash}OSC_OUT(5T)-Pad6)") (class "Default")
      (node (ref "U$2") (pin "6") (pinfunction "PH1/OSC_OUT(5T)_6") (pintype "bidirectional"))
    )
    (net (code "102") (name "unconnected-(U$2-VBAT-Pad1)") (class "Default")
      (node (ref "U$2") (pin "1") (pinfunction "VBAT_1") (pintype "bidirectional"))
    )
    (net (code "103") (name "unconnected-(U$2-VCAP_1-Pad30)") (class "Default")
      (node (ref "U$2") (pin "30") (pinfunction "VCAP_1_30") (pintype "bidirectional"))
    )
    (net (code "104") (name "unconnected-(U$2-VSS_1-Pad18)") (class "Default")
      (node (ref "U$2") (pin "18") (pinfunction "VSS_1_18") (pintype "bidirectional"))
    )
    (net (code "105") (name "unconnected-(U$2-VSS_2-Pad31)") (class "Default")
      (node (ref "U$2") (pin "31") (pinfunction "VSS_2_31") (pintype "bidirectional"))
    )
    (net (code "106") (name "unconnected-(U$2-VSS_3-Pad47)") (class "Default")
      (node (ref "U$2") (pin "47") (pinfunction "VSS_3_47") (pintype "bidirectional"))
    )
    (net (code "107") (name "unconnected-(U$2-VSS_4-Pad63)") (class "Default")
      (node (ref "U$2") (pin "63") (pinfunction "VSS_4_63") (pintype "bidirectional"))
    )
    (net (code "108") (name "unconnected-(U$3-PadPAD)") (class "Default")
      (node (ref "U$3") (pin "PAD") (pinfunction "PAD_PAD") (pintype "bidirectional"))
    )
  )
)
